# flt.net
KiCad netlist of a schematic drawn in EAGLE
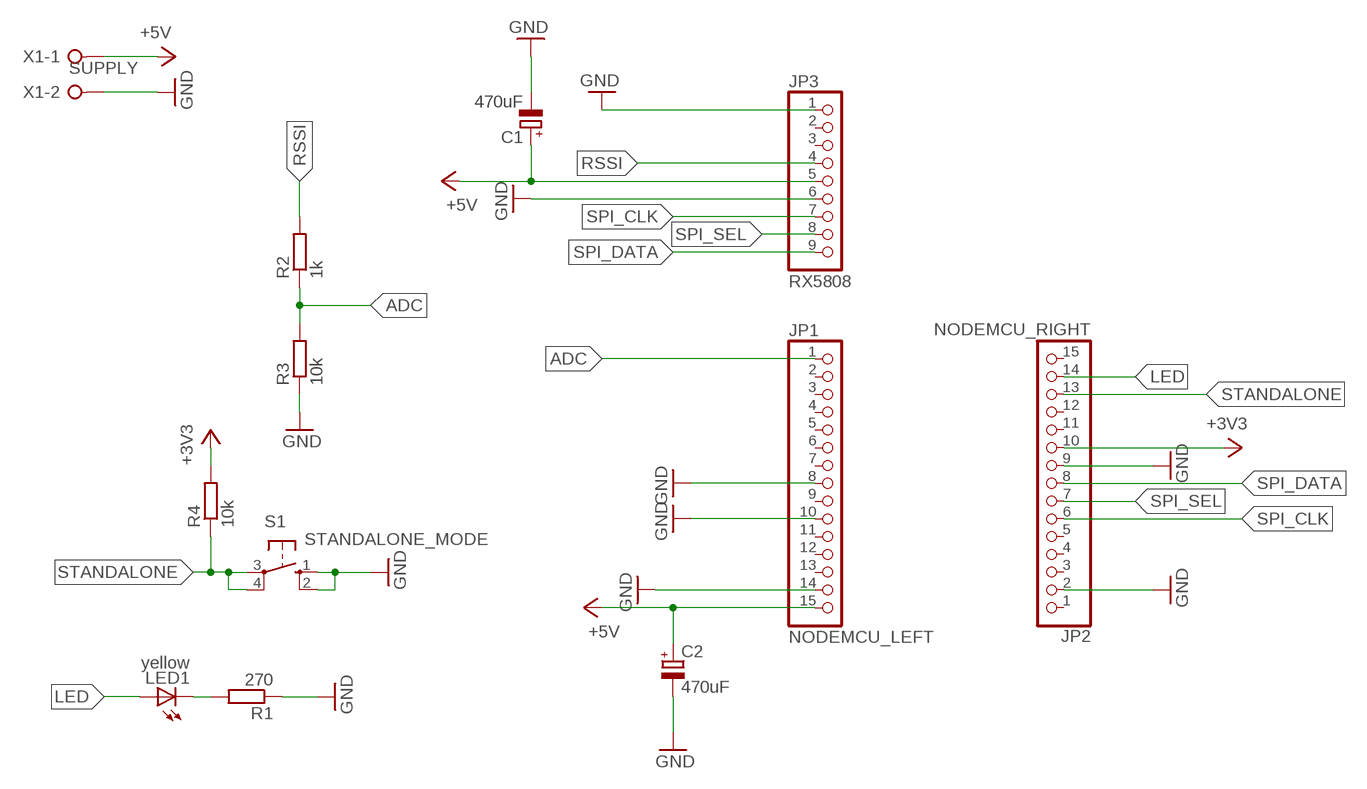
[diagram p0: schematic, sheet 1]

(export (version "E")
  (design (tool "Eeschema 10.0.6"))
  (components
    (comp (ref "C1")
      (value "470uF")
      (footprint "eagle-import:E5-8,5")
      (libsource (lib "eagle-import") (part "CPOL-EUE5-8.5"))
    )
    (comp (ref "C2")
      (value "470uF")
      (footprint "eagle-import:E5-8,5")
      (libsource (lib "eagle-import") (part "CPOL-EUE5-8.5"))
    )
    (comp (ref "JP1")
      (value "NODEMCU_LEFT")
      (footprint "eagle-import:1X15")
      (libsource (lib "eagle-import") (part "PINHD-1X15"))
    )
    (comp (ref "JP2")
      (value "NODEMCU_RIGHT")
      (footprint "eagle-import:1X15")
      (libsource (lib "eagle-import") (part "PINHD-1X15"))
    )
    (comp (ref "JP3")
      (value "RX5808")
      (footprint "eagle-import:1X09")
      (libsource (lib "eagle-import") (part "PINHD-1X9"))
    )
    (comp (ref "LED1")
      (value "yellow")
      (footprint "eagle-import:LED5MM")
      (libsource (lib "eagle-import") (part "LED5MM"))
    )
    (comp (ref "R1")
      (value "270")
      (footprint "eagle-import:0204_7")
      (libsource (lib "eagle-import") (part "R-EU_0204/7"))
    )
    (comp (ref "R2")
      (value "1k")
      (footprint "eagle-import:0204_7")
      (libsource (lib "eagle-import") (part "R-EU_0204/7"))
    )
    (comp (ref "R3")
      (value "10k")
      (footprint "eagle-import:0204_7")
      (libsource (lib "eagle-import") (part "R-EU_0204/7"))
    )
    (comp (ref "R4")
      (value "10k")
      (footprint "eagle-import:0204_7")
      (libsource (lib "eagle-import") (part "R-EU_0204/7"))
    )
    (comp (ref "S1")
      (value "STANDALONE_MODE")
      (footprint "eagle-import:B3F-10XX")
      (fields (field (name "MPN") "B3F-1000"))
      (libsource (lib "eagle-import") (part "10-XX"))
    )
    (comp (ref "X1")
      (value "SUPPLY")
      (footprint "eagle-import:W237-132")
      (libsource (lib "eagle-import") (part "W237-02P"))
    )
  )
  (nets
    (net (code "1") (name "+3V3") (class "Default")
      (node (ref "JP2") (pin "10") (pinfunction "10_10") (pintype "passive"))
      (node (ref "R4") (pin "2") (pinfunction "2_2") (pintype "passive"))
    )
    (net (code "2") (name "+5V") (class "Default")
      (node (ref "C1") (pin "+") (pinfunction "+_+") (pintype "passive"))
      (node (ref "C2") (pin "+") (pinfunction "+_+") (pintype "passive"))
      (node (ref "JP1") (pin "15") (pinfunction "15_15") (pintype "passive"))
      (node (ref "JP3") (pin "5") (pinfunction "5_5") (pintype "passive"))
      (node (ref "X1") (pin "1") (pinfunction "KL_1") (pintype "passive"))
    )
    (net (code "3") (name "ADC") (class "Default")
      (node (ref "JP1") (pin "1") (pinfunction "1_1") (pintype "passive"))
      (node (ref "R2") (pin "1") (pinfunction "1_1") (pintype "passive"))
      (node (ref "R3") (pin "2") (pinfunction "2_2") (pintype "passive"))
    )
    (net (code "4") (name "GND") (class "Default")
      (node (ref "C1") (pin "-") (pinfunction "-_-") (pintype "passive"))
      (node (ref "C2") (pin "-") (pinfunction "-_-") (pintype "passive"))
      (node (ref "JP1") (pin "10") (pinfunction "10_10") (pintype "passive"))
      (node (ref "JP1") (pin "14") (pinfunction "14_14") (pintype "passive"))
      (node (ref "JP1") (pin "8") (pinfunction "8_8") (pintype "passive"))
      (node (ref "JP2") (pin "2") (pinfunction "2_2") (pintype "passive"))
      (node (ref "JP2") (pin "9") (pinfunction "9_9") (pintype "passive"))
      (node (ref "JP3") (pin "1") (pinfunction "1_1") (pintype "passive"))
      (node (ref "JP3") (pin "6") (pinfunction "6_6") (pintype "passive"))
      (node (ref "R1") (pin "1") (pinfunction "1_1") (pintype "passive"))
      (node (ref "R3") (pin "1") (pinfunction "1_1") (pintype "passive"))
      (node (ref "S1") (pin "1") (pinfunction "S_1") (pintype "passive"))
      (node (ref "S1") (pin "2") (pinfunction "S1_2") (pintype "passive"))
      (node (ref "X1") (pin "2") (pinfunction "KL_2") (pintype "passive"))
    )
    (net (code "5") (name "LED") (class "Default")
      (node (ref "JP2") (pin "14") (pinfunction "14_14") (pintype "passive"))
      (node (ref "LED1") (pin "A") (pinfunction "A_A") (pintype "passive"))
    )
    (net (code "6") (name "Net-(LED1-C)") (class "Default")
      (node (ref "LED1") (pin "K") (pinfunction "C_K") (pintype "passive"))
      (node (ref "R1") (pin "2") (pinfunction "2_2") (pintype "passive"))
    )
    (net (code "7") (name "RSSI") (class "Default")
      (node (ref "JP3") (pin "4") (pinfunction "4_4") (pintype "passive"))
      (node (ref "R2") (pin "2") (pinfunction "2_2") (pintype "passive"))
    )
    (net (code "8") (name "SPI_CLK") (class "Default")
      (node (ref "JP2") (pin "6") (pinfunction "6_6") (pintype "passive"))
      (node (ref "JP3") (pin "7") (pinfunction "7_7") (pintype "passive"))
    )
    (net (code "9") (name "SPI_DATA") (class "Default")
      (node (ref "JP2") (pin "8") (pinfunction "8_8") (pintype "passive"))
      (node (ref "JP3") (pin "9") (pinfunction "9_9") (pintype "passive"))
    )
    (net (code "10") (name "SPI_SEL") (class "Default")
      (node (ref "JP2") (pin "7") (pinfunction "7_7") (pintype "passive"))
      (node (ref "JP3") (pin "8") (pinfunction "8_8") (pintype "passive"))
    )
    (net (code "11") (name "STANDALONE") (class "Default")
      (node (ref "JP2") (pin "13") (pinfunction "13_13") (pintype "passive"))
      (node (ref "R4") (pin "1") (pinfunction "1_1") (pintype "passive"))
      (node (ref "S1") (pin "3") (pinfunction "P_3") (pintype "passive"))
      (node (ref "S1") (pin "4") (pinfunction "P1_4") (pintype "passive"))
    )
    (net (code "12") (name "unconnected-(JP1-Pad2)") (class "Default")
      (node (ref "JP1") (pin "2") (pinfunction "2_2") (pintype "passive"))
    )
    (net (code "13") (name "unconnected-(JP1-Pad3)") (class "Default")
      (node (ref "JP1") (pin "3") (pinfunction "3_3") (pintype "passive"))
    )
    (net (code "14") (name "unconnected-(JP1-Pad4)") (class "Default")
      (node (ref "JP1") (pin "4") (pinfunction "4_4") (pintype "passive"))
    )
    (net (code "15") (name "unconnected-(JP1-Pad5)") (class "Default")
      (node (ref "JP1") (pin "5") (pinfunction "5_5") (pintype "passive"))
    )
    (net (code "16") (name "unconnected-(JP1-Pad6)") (class "Default")
      (node (ref "JP1") (pin "6") (pinfunction "6_6") (pintype "passive"))
    )
    (net (code "17") (name "unconnected-(JP1-Pad7)") (class "Default")
      (node (ref "JP1") (pin "7") (pinfunction "7_7") (pintype "passive"))
    )
    (net (code "18") (name "unconnected-(JP1-Pad9)") (class "Default")
      (node (ref "JP1") (pin "9") (pinfunction "9_9") (pintype "passive"))
    )
    (net (code "19") (name "unconnected-(JP1-Pad11)") (class "Default")
      (node (ref "JP1") (pin "11") (pinfunction "11_11") (pintype "passive"))
    )
    (net (code "20") (name "unconnected-(JP1-Pad12)") (class "Default")
      (node (ref "JP1") (pin "12") (pinfunction "12_12") (pintype "passive"))
    )
    (net (code "21") (name "unconnected-(JP1-Pad13)") (class "Default")
      (node (ref "JP1") (pin "13") (pinfunction "13_13") (pintype "passive"))
    )
    (net (code "22") (name "unconnected-(JP2-Pad1)") (class "Default")
      (node (ref "JP2") (pin "1") (pinfunction "1_1") (pintype "passive"))
    )
    (net (code "23") (name "unconnected-(JP2-Pad3)") (class "Default")
      (node (ref "JP2") (pin "3") (pinfunction "3_3") (pintype "passive"))
    )
    (net (code "24") (name "unconnected-(JP2-Pad4)") (class "Default")
      (node (ref "JP2") (pin "4") (pinfunction "4_4") (pintype "passive"))
    )
    (net (code "25") (name "unconnected-(JP2-Pad5)") (class "Default")
      (node (ref "JP2") (pin "5") (pinfunction "5_5") (pintype "passive"))
    )
    (net (code "26") (name "unconnected-(JP2-Pad11)") (class "Default")
      (node (ref "JP2") (pin "11") (pinfunction "11_11") (pintype "passive"))
    )
    (net (code "27") (name "unconnected-(JP2-Pad12)") (class "Default")
      (node (ref "JP2") (pin "12") (pinfunction "12_12") (pintype "passive"))
    )
    (net (code "28") (name "unconnected-(JP2-Pad15)") (class "Default")
      (node (ref "JP2") (pin "15") (pinfunction "15_15") (pintype "passive"))
    )
    (net (code "29") (name "unconnected-(JP3-Pad2)") (class "Default")
      (node (ref "JP3") (pin "2") (pinfunction "2_2") (pintype "passive"))
    )
    (net (code "30") (name "unconnected-(JP3-Pad3)") (class "Default")
      (node (ref "JP3") (pin "3") (pinfunction "3_3") (pintype "passive"))
    )
  )
)
